# Flight_Controller.net
KiCad netlist of a schematic drawn in EAGLE
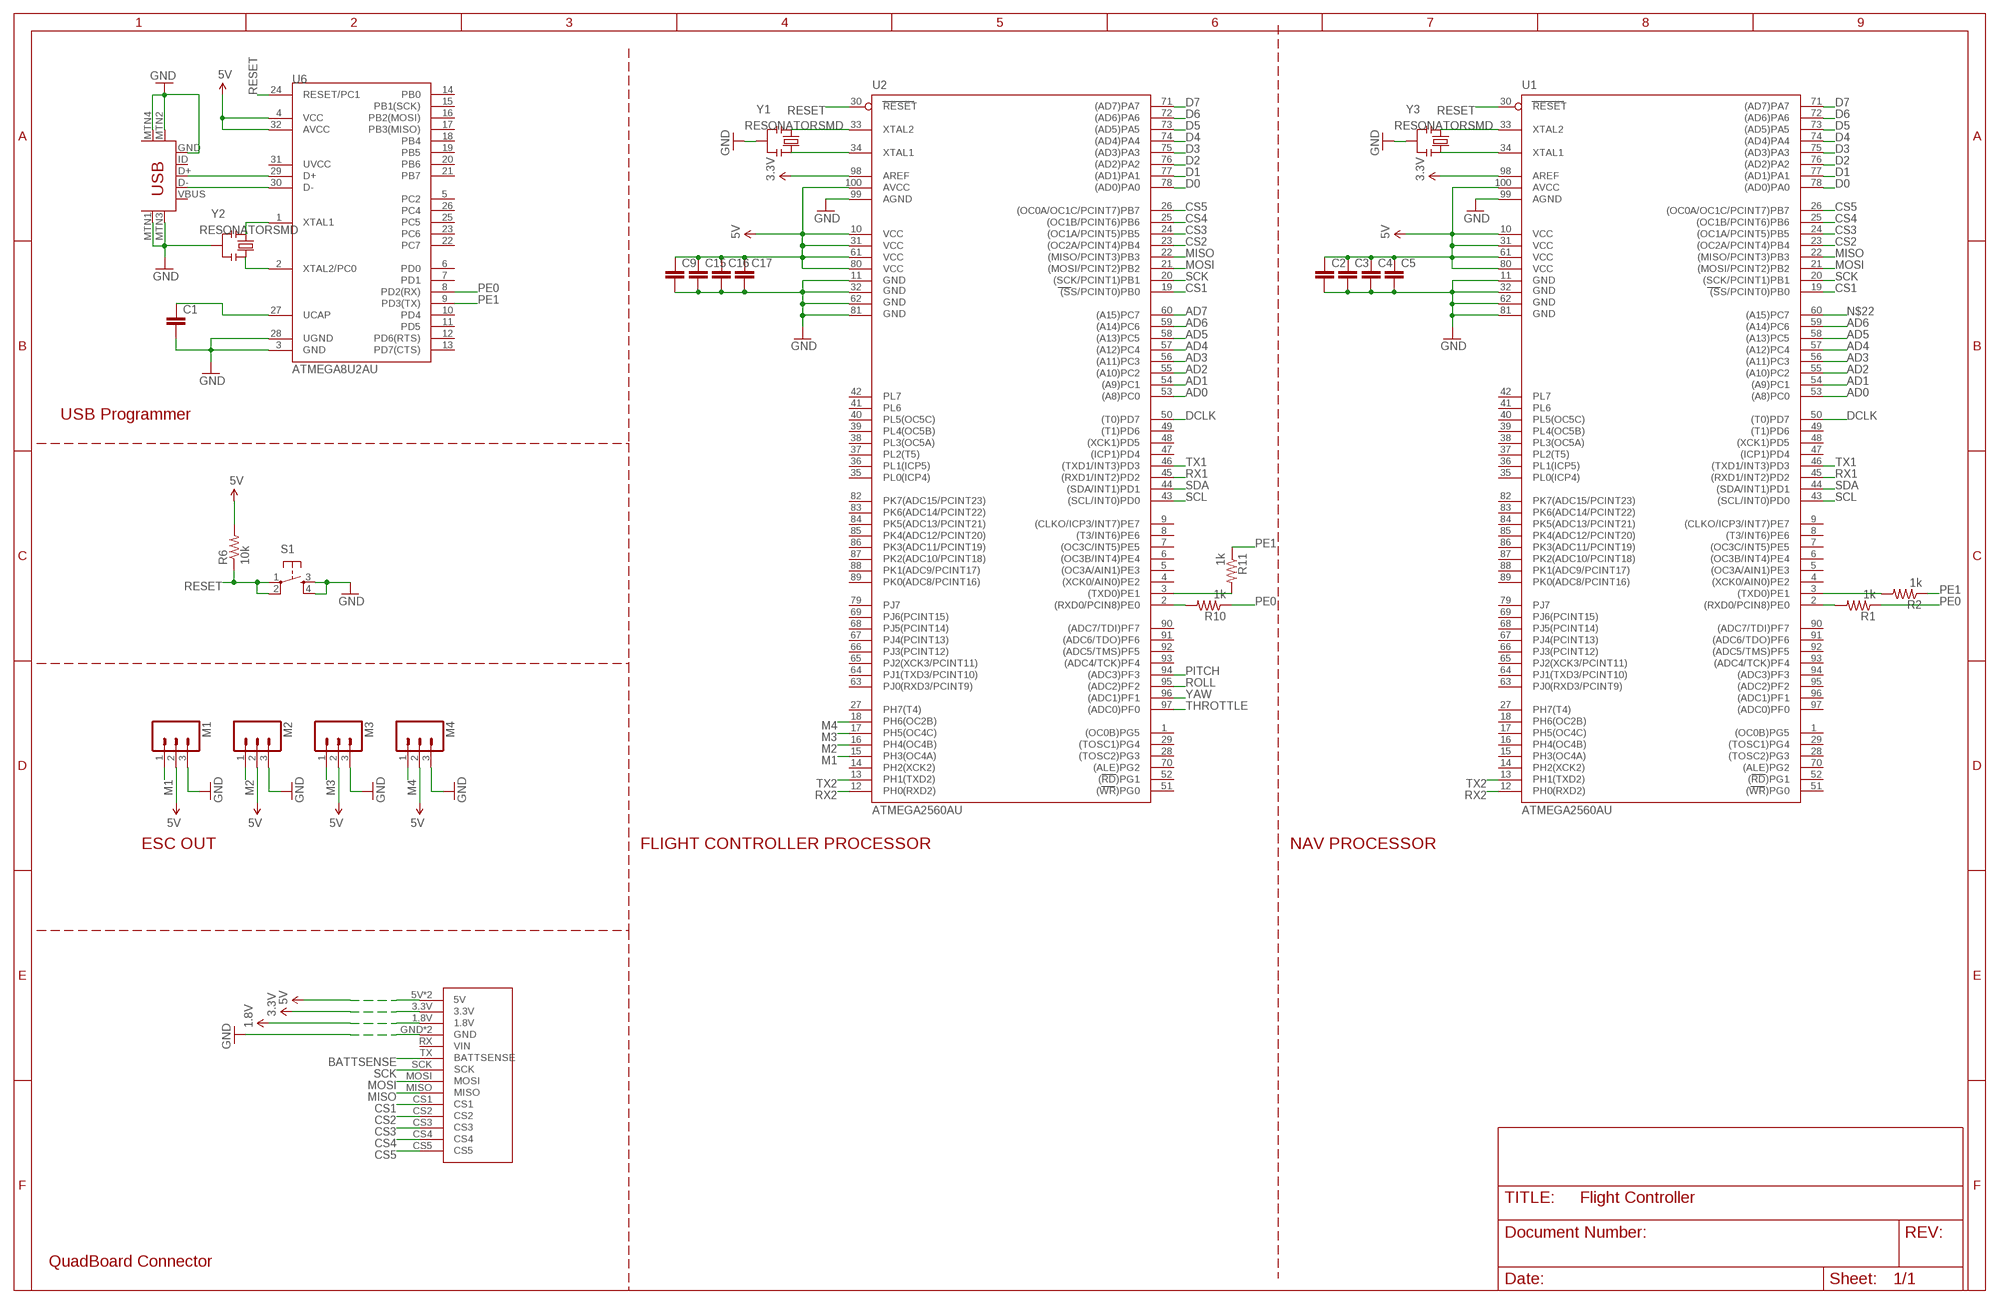
[diagram p0: schematic, sheet 1]

(export (version "E")
  (design (tool "Eeschema 10.0.6"))
  (components
    (comp (ref "C1")
      (value "CAP0805")
      (footprint "eagle-import:0805")
      (libsource (lib "eagle-import") (part "CAP0805"))
    )
    (comp (ref "C2")
      (value "CAP0805")
      (footprint "eagle-import:0805")
      (libsource (lib "eagle-import") (part "CAP0805"))
    )
    (comp (ref "C3")
      (value "CAP0805")
      (footprint "eagle-import:0805")
      (libsource (lib "eagle-import") (part "CAP0805"))
    )
    (comp (ref "C4")
      (value "CAP0805")
      (footprint "eagle-import:0805")
      (libsource (lib "eagle-import") (part "CAP0805"))
    )
    (comp (ref "C5")
      (value "CAP0805")
      (footprint "eagle-import:0805")
      (libsource (lib "eagle-import") (part "CAP0805"))
    )
    (comp (ref "C9")
      (value "CAP0805")
      (footprint "eagle-import:0805")
      (libsource (lib "eagle-import") (part "CAP0805"))
    )
    (comp (ref "C15")
      (value "CAP0805")
      (footprint "eagle-import:0805")
      (libsource (lib "eagle-import") (part "CAP0805"))
    )
    (comp (ref "C16")
      (value "CAP0805")
      (footprint "eagle-import:0805")
      (libsource (lib "eagle-import") (part "CAP0805"))
    )
    (comp (ref "C17")
      (value "CAP0805")
      (footprint "eagle-import:0805")
      (libsource (lib "eagle-import") (part "CAP0805"))
    )
    (comp (ref "M1")
      (value "M03PTH")
      (footprint "eagle-import:1X03")
      (libsource (lib "eagle-import") (part "M03PTH"))
    )
    (comp (ref "M2")
      (value "M03PTH")
      (footprint "eagle-import:1X03")
      (libsource (lib "eagle-import") (part "M03PTH"))
    )
    (comp (ref "M3")
      (value "M03PTH")
      (footprint "eagle-import:1X03")
      (libsource (lib "eagle-import") (part "M03PTH"))
    )
    (comp (ref "M4")
      (value "M03PTH")
      (footprint "eagle-import:1X03")
      (libsource (lib "eagle-import") (part "M03PTH"))
    )
    (comp (ref "R1")
      (value "1k")
      (footprint "eagle-import:0805")
      (libsource (lib "eagle-import") (part "RESISTOR0805-RES"))
    )
    (comp (ref "R2")
      (value "1k")
      (footprint "eagle-import:0805")
      (libsource (lib "eagle-import") (part "RESISTOR0805-RES"))
    )
    (comp (ref "R6")
      (value "10k")
      (footprint "eagle-import:0805")
      (libsource (lib "eagle-import") (part "RESISTOR0805-RES"))
    )
    (comp (ref "R10")
      (value "1k")
      (footprint "eagle-import:0805")
      (libsource (lib "eagle-import") (part "RESISTOR0805-RES"))
    )
    (comp (ref "R11")
      (value "1k")
      (footprint "eagle-import:0805")
      (libsource (lib "eagle-import") (part "RESISTOR0805-RES"))
    )
    (comp (ref "S1")
      (value "TAC_SWITCHSMD")
      (footprint "eagle-import:TACTILE_SWITCH_SMD")
      (libsource (lib "eagle-import") (part "TAC_SWITCHSMD"))
    )
    (comp (ref "U$1")
      (value "QUADBOARDEXT")
      (footprint "eagle-import:QUADBOARDEXT")
      (libsource (lib "eagle-import") (part "QUADBOARDEXT"))
    )
    (comp (ref "U$2")
      (value "USB-MINIB-5PIN")
      (footprint "eagle-import:USB-MINIB")
      (libsource (lib "eagle-import") (part "USB-MINIB-5PIN"))
    )
    (comp (ref "U1")
      (value "ATMEGA2560AU")
      (footprint "eagle-import:TQFP100")
      (libsource (lib "eagle-import") (part "ATMEGA2560AU"))
    )
    (comp (ref "U2")
      (value "ATMEGA2560AU")
      (footprint "eagle-import:TQFP100")
      (libsource (lib "eagle-import") (part "ATMEGA2560AU"))
    )
    (comp (ref "U6")
      (value "ATMEGA8U2AU")
      (footprint "eagle-import:TQFP32-08")
      (libsource (lib "eagle-import") (part "ATMEGA8U2AU"))
    )
    (comp (ref "Y1")
      (value "RESONATORSMD")
      (footprint "eagle-import:RESONATOR-SMD")
      (libsource (lib "eagle-import") (part "RESONATORSMD"))
    )
    (comp (ref "Y2")
      (value "RESONATORSMD")
      (footprint "eagle-import:RESONATOR-SMD")
      (libsource (lib "eagle-import") (part "RESONATORSMD"))
    )
    (comp (ref "Y3")
      (value "RESONATORSMD")
      (footprint "eagle-import:RESONATOR-SMD")
      (libsource (lib "eagle-import") (part "RESONATORSMD"))
    )
  )
  (nets
    (net (code "1") (name "/AD0") (class "Default")
      (node (ref "U1") (pin "53") (pinfunction "(A8)PC0_53") (pintype "bidirectional"))
      (node (ref "U2") (pin "53") (pinfunction "(A8)PC0_53") (pintype "bidirectional"))
    )
    (net (code "2") (name "/AD1") (class "Default")
      (node (ref "U1") (pin "54") (pinfunction "(A9)PC1_54") (pintype "bidirectional"))
      (node (ref "U2") (pin "54") (pinfunction "(A9)PC1_54") (pintype "bidirectional"))
    )
    (net (code "3") (name "/AD2") (class "Default")
      (node (ref "U1") (pin "55") (pinfunction "(A10)PC2_55") (pintype "bidirectional"))
      (node (ref "U2") (pin "55") (pinfunction "(A10)PC2_55") (pintype "bidirectional"))
    )
    (net (code "4") (name "/AD3") (class "Default")
      (node (ref "U1") (pin "56") (pinfunction "(A11)PC3_56") (pintype "bidirectional"))
      (node (ref "U2") (pin "56") (pinfunction "(A11)PC3_56") (pintype "bidirectional"))
    )
    (net (code "5") (name "/AD4") (class "Default")
      (node (ref "U1") (pin "57") (pinfunction "(A12)PC4_57") (pintype "bidirectional"))
      (node (ref "U2") (pin "57") (pinfunction "(A12)PC4_57") (pintype "bidirectional"))
    )
    (net (code "6") (name "/AD5") (class "Default")
      (node (ref "U1") (pin "58") (pinfunction "(A13)PC5_58") (pintype "bidirectional"))
      (node (ref "U2") (pin "58") (pinfunction "(A13)PC5_58") (pintype "bidirectional"))
    )
    (net (code "7") (name "/AD6") (class "Default")
      (node (ref "U1") (pin "59") (pinfunction "(A14)PC6_59") (pintype "bidirectional"))
      (node (ref "U2") (pin "59") (pinfunction "(A14)PC6_59") (pintype "bidirectional"))
    )
    (net (code "8") (name "/AD7") (class "Default")
      (node (ref "U2") (pin "60") (pinfunction "(A15)PC7_60") (pintype "bidirectional"))
    )
    (net (code "9") (name "/BATTSENSE") (class "Default")
      (node (ref "U$1") (pin "TX") (pinfunction "BATTSENSE_TX") (pintype "bidirectional"))
    )
    (net (code "10") (name "/CS1") (class "Default")
      (node (ref "U$1") (pin "CS1") (pinfunction "CS1_CS1") (pintype "bidirectional"))
      (node (ref "U1") (pin "19") (pinfunction "(SS/PCINT0)PB0_19") (pintype "bidirectional"))
      (node (ref "U2") (pin "19") (pinfunction "(SS/PCINT0)PB0_19") (pintype "bidirectional"))
    )
    (net (code "11") (name "/CS2") (class "Default")
      (node (ref "U$1") (pin "CS2") (pinfunction "CS2_CS2") (pintype "bidirectional"))
      (node (ref "U1") (pin "23") (pinfunction "(OC2A/PCINT4)PB4_23") (pintype "bidirectional"))
      (node (ref "U2") (pin "23") (pinfunction "(OC2A/PCINT4)PB4_23") (pintype "bidirectional"))
    )
    (net (code "12") (name "/CS3") (class "Default")
      (node (ref "U$1") (pin "CS3") (pinfunction "CS3_CS3") (pintype "bidirectional"))
      (node (ref "U1") (pin "24") (pinfunction "(OC1A/PCINT5)PB5_24") (pintype "bidirectional"))
      (node (ref "U2") (pin "24") (pinfunction "(OC1A/PCINT5)PB5_24") (pintype "bidirectional"))
    )
    (net (code "13") (name "/CS4") (class "Default")
      (node (ref "U$1") (pin "CS4") (pinfunction "CS4_CS4") (pintype "bidirectional"))
      (node (ref "U1") (pin "25") (pinfunction "(OC1B/PCINT6)PB6_25") (pintype "bidirectional"))
      (node (ref "U2") (pin "25") (pinfunction "(OC1B/PCINT6)PB6_25") (pintype "bidirectional"))
    )
    (net (code "14") (name "/CS5") (class "Default")
      (node (ref "U$1") (pin "CS5") (pinfunction "CS5_CS5") (pintype "bidirectional"))
      (node (ref "U1") (pin "26") (pinfunction "(OC0A/OC1C/PCINT7)PB7_26") (pintype "bidirectional"))
      (node (ref "U2") (pin "26") (pinfunction "(OC0A/OC1C/PCINT7)PB7_26") (pintype "bidirectional"))
    )
    (net (code "15") (name "/D0") (class "Default")
      (node (ref "U1") (pin "78") (pinfunction "(AD0)PA0_78") (pintype "bidirectional"))
      (node (ref "U2") (pin "78") (pinfunction "(AD0)PA0_78") (pintype "bidirectional"))
    )
    (net (code "16") (name "/D1") (class "Default")
      (node (ref "U1") (pin "77") (pinfunction "(AD1)PA1_77") (pintype "bidirectional"))
      (node (ref "U2") (pin "77") (pinfunction "(AD1)PA1_77") (pintype "bidirectional"))
    )
    (net (code "17") (name "/D2") (class "Default")
      (node (ref "U1") (pin "76") (pinfunction "(AD2)PA2_76") (pintype "bidirectional"))
      (node (ref "U2") (pin "76") (pinfunction "(AD2)PA2_76") (pintype "bidirectional"))
    )
    (net (code "18") (name "/D3") (class "Default")
      (node (ref "U1") (pin "75") (pinfunction "(AD3)PA3_75") (pintype "bidirectional"))
      (node (ref "U2") (pin "75") (pinfunction "(AD3)PA3_75") (pintype "bidirectional"))
    )
    (net (code "19") (name "/D4") (class "Default")
      (node (ref "U1") (pin "74") (pinfunction "(AD4)PA4_74") (pintype "bidirectional"))
      (node (ref "U2") (pin "74") (pinfunction "(AD4)PA4_74") (pintype "bidirectional"))
    )
    (net (code "20") (name "/D5") (class "Default")
      (node (ref "U1") (pin "73") (pinfunction "(AD5)PA5_73") (pintype "bidirectional"))
      (node (ref "U2") (pin "73") (pinfunction "(AD5)PA5_73") (pintype "bidirectional"))
    )
    (net (code "21") (name "/D6") (class "Default")
      (node (ref "U1") (pin "72") (pinfunction "(AD6)PA6_72") (pintype "bidirectional"))
      (node (ref "U2") (pin "72") (pinfunction "(AD6)PA6_72") (pintype "bidirectional"))
    )
    (net (code "22") (name "/D7") (class "Default")
      (node (ref "U1") (pin "71") (pinfunction "(AD7)PA7_71") (pintype "bidirectional"))
      (node (ref "U2") (pin "71") (pinfunction "(AD7)PA7_71") (pintype "bidirectional"))
    )
    (net (code "23") (name "/DCLK") (class "Default")
      (node (ref "U1") (pin "50") (pinfunction "(T0)PD7_50") (pintype "bidirectional"))
      (node (ref "U2") (pin "50") (pinfunction "(T0)PD7_50") (pintype "bidirectional"))
    )
    (net (code "24") (name "/M1") (class "Default")
      (node (ref "M1") (pin "1") (pinfunction "1_1") (pintype "passive"))
      (node (ref "U2") (pin "15") (pinfunction "PH3(OC4A)_15") (pintype "bidirectional"))
    )
    (net (code "25") (name "/M2") (class "Default")
      (node (ref "M2") (pin "1") (pinfunction "1_1") (pintype "passive"))
      (node (ref "U2") (pin "16") (pinfunction "PH4(OC4B)_16") (pintype "bidirectional"))
    )
    (net (code "26") (name "/M3") (class "Default")
      (node (ref "M3") (pin "1") (pinfunction "1_1") (pintype "passive"))
      (node (ref "U2") (pin "17") (pinfunction "PH5(OC4C)_17") (pintype "bidirectional"))
    )
    (net (code "27") (name "/M4") (class "Default")
      (node (ref "M4") (pin "1") (pinfunction "1_1") (pintype "passive"))
      (node (ref "U2") (pin "18") (pinfunction "PH6(OC2B)_18") (pintype "bidirectional"))
    )
    (net (code "28") (name "/MISO") (class "Default")
      (node (ref "U$1") (pin "MISO") (pinfunction "MISO_MISO") (pintype "bidirectional"))
      (node (ref "U1") (pin "22") (pinfunction "(MISO/PCINT3)PB3_22") (pintype "bidirectional"))
      (node (ref "U2") (pin "22") (pinfunction "(MISO/PCINT3)PB3_22") (pintype "bidirectional"))
    )
    (net (code "29") (name "/MOSI") (class "Default")
      (node (ref "U$1") (pin "MOSI") (pinfunction "MOSI_MOSI") (pintype "bidirectional"))
      (node (ref "U1") (pin "21") (pinfunction "(MOSI/PCINT2)PB2_21") (pintype "bidirectional"))
      (node (ref "U2") (pin "21") (pinfunction "(MOSI/PCINT2)PB2_21") (pintype "bidirectional"))
    )
    (net (code "30") (name "/N$22") (class "Default")
      (node (ref "U1") (pin "60") (pinfunction "(A15)PC7_60") (pintype "bidirectional"))
    )
    (net (code "31") (name "/PE0") (class "Default")
      (node (ref "R1") (pin "1") (pinfunction "1_1") (pintype "passive"))
      (node (ref "R10") (pin "1") (pinfunction "1_1") (pintype "passive"))
      (node (ref "U6") (pin "8") (pinfunction "PD2(RX)_8") (pintype "bidirectional"))
    )
    (net (code "32") (name "/PE1") (class "Default")
      (node (ref "R11") (pin "1") (pinfunction "1_1") (pintype "passive"))
      (node (ref "R2") (pin "1") (pinfunction "1_1") (pintype "passive"))
      (node (ref "U6") (pin "9") (pinfunction "PD3(TX)_9") (pintype "bidirectional"))
    )
    (net (code "33") (name "/PITCH") (class "Default")
      (node (ref "U2") (pin "94") (pinfunction "(ADC3)PF3_94") (pintype "bidirectional"))
    )
    (net (code "34") (name "/RESET") (class "Default")
      (node (ref "R6") (pin "1") (pinfunction "1_1") (pintype "passive"))
      (node (ref "S1") (pin "1") (pinfunction "1_1") (pintype "passive"))
      (node (ref "S1") (pin "2") (pinfunction "2_2") (pintype "passive"))
      (node (ref "U1") (pin "30") (pinfunction "RESET_30") (pintype "input"))
      (node (ref "U2") (pin "30") (pinfunction "RESET_30") (pintype "input"))
      (node (ref "U6") (pin "24") (pinfunction "RESET/PC1_24") (pintype "bidirectional"))
    )
    (net (code "35") (name "/ROLL") (class "Default")
      (node (ref "U2") (pin "95") (pinfunction "(ADC2)PF2_95") (pintype "bidirectional"))
    )
    (net (code "36") (name "/RX1") (class "Default")
      (node (ref "U1") (pin "45") (pinfunction "(RXD1/INT2)PD2_45") (pintype "bidirectional"))
      (node (ref "U2") (pin "45") (pinfunction "(RXD1/INT2)PD2_45") (pintype "bidirectional"))
    )
    (net (code "37") (name "/RX2") (class "Default")
      (node (ref "U1") (pin "12") (pinfunction "PH0(RXD2)_12") (pintype "bidirectional"))
      (node (ref "U2") (pin "12") (pinfunction "PH0(RXD2)_12") (pintype "bidirectional"))
    )
    (net (code "38") (name "/SCK") (class "Default")
      (node (ref "U$1") (pin "SCK") (pinfunction "SCK_SCK") (pintype "bidirectional"))
      (node (ref "U1") (pin "20") (pinfunction "(SCK/PCINT1)PB1_20") (pintype "bidirectional"))
      (node (ref "U2") (pin "20") (pinfunction "(SCK/PCINT1)PB1_20") (pintype "bidirectional"))
    )
    (net (code "39") (name "/SCL") (class "Default")
      (node (ref "U1") (pin "43") (pinfunction "(SCL/INT0)PD0_43") (pintype "bidirectional"))
      (node (ref "U2") (pin "43") (pinfunction "(SCL/INT0)PD0_43") (pintype "bidirectional"))
    )
    (net (code "40") (name "/SDA") (class "Default")
      (node (ref "U1") (pin "44") (pinfunction "(SDA/INT1)PD1_44") (pintype "bidirectional"))
      (node (ref "U2") (pin "44") (pinfunction "(SDA/INT1)PD1_44") (pintype "bidirectional"))
    )
    (net (code "41") (name "/THROTTLE") (class "Default")
      (node (ref "U2") (pin "97") (pinfunction "(ADC0)PF0_97") (pintype "bidirectional"))
    )
    (net (code "42") (name "/TX1") (class "Default")
      (node (ref "U1") (pin "46") (pinfunction "(TXD1/INT3)PD3_46") (pintype "bidirectional"))
      (node (ref "U2") (pin "46") (pinfunction "(TXD1/INT3)PD3_46") (pintype "bidirectional"))
    )
    (net (code "43") (name "/TX2") (class "Default")
      (node (ref "U1") (pin "13") (pinfunction "PH1(TXD2)_13") (pintype "bidirectional"))
      (node (ref "U2") (pin "13") (pinfunction "PH1(TXD2)_13") (pintype "bidirectional"))
    )
    (net (code "44") (name "/YAW") (class "Default")
      (node (ref "U2") (pin "96") (pinfunction "(ADC1)PF1_96") (pintype "bidirectional"))
    )
    (net (code "45") (name "1.8V") (class "Default")
      (node (ref "U$1") (pin "1.8V") (pinfunction "1.8V_1.8V") (pintype "bidirectional"))
    )
    (net (code "46") (name "3.3V") (class "Default")
      (node (ref "U$1") (pin "3.3V") (pinfunction "3.3V_3.3V") (pintype "bidirectional"))
      (node (ref "U1") (pin "98") (pinfunction "AREF_98") (pintype "bidirectional"))
      (node (ref "U2") (pin "98") (pinfunction "AREF_98") (pintype "bidirectional"))
    )
    (net (code "47") (name "5V") (class "Default")
      (node (ref "C15") (pin "1") (pinfunction "1_1") (pintype "passive"))
      (node (ref "C16") (pin "1") (pinfunction "1_1") (pintype "passive"))
      (node (ref "C17") (pin "1") (pinfunction "1_1") (pintype "passive"))
      (node (ref "C2") (pin "1") (pinfunction "1_1") (pintype "passive"))
      (node (ref "C3") (pin "1") (pinfunction "1_1") (pintype "passive"))
      (node (ref "C4") (pin "1") (pinfunction "1_1") (pintype "passive"))
      (node (ref "C5") (pin "1") (pinfunction "1_1") (pintype "passive"))
      (node (ref "C9") (pin "1") (pinfunction "1_1") (pintype "passive"))
      (node (ref "M1") (pin "2") (pinfunction "2_2") (pintype "passive"))
      (node (ref "M2") (pin "2") (pinfunction "2_2") (pintype "passive"))
      (node (ref "M3") (pin "2") (pinfunction "2_2") (pintype "passive"))
      (node (ref "M4") (pin "2") (pinfunction "2_2") (pintype "passive"))
      (node (ref "R6") (pin "2") (pinfunction "2_2") (pintype "passive"))
      (node (ref "U$1") (pin "5V") (pinfunction "5V_5V") (pintype "bidirectional"))
      (node (ref "U$1") (pin "5V1") (pinfunction "5V_5V1") (pintype "bidirectional"))
      (node (ref "U1") (pin "10") (pinfunction "VCC_10") (pintype "power_in"))
      (node (ref "U1") (pin "100") (pinfunction "AVCC_100") (pintype "power_in"))
      (node (ref "U1") (pin "31") (pinfunction "VCC1_31") (pintype "power_in"))
      (node (ref "U1") (pin "61") (pinfunction "VCC2_61") (pintype "power_in"))
      (node (ref "U1") (pin "80") (pinfunction "VCC3_80") (pintype "power_in"))
      (node (ref "U2") (pin "10") (pinfunction "VCC_10") (pintype "power_in"))
      (node (ref "U2") (pin "100") (pinfunction "AVCC_100") (pintype "power_in"))
      (node (ref "U2") (pin "31") (pinfunction "VCC1_31") (pintype "power_in"))
      (node (ref "U2") (pin "61") (pinfunction "VCC2_61") (pintype "power_in"))
      (node (ref "U2") (pin "80") (pinfunction "VCC3_80") (pintype "power_in"))
      (node (ref "U6") (pin "32") (pinfunction "AVCC_32") (pintype "bidirectional"))
      (node (ref "U6") (pin "4") (pinfunction "VCC_4") (pintype "bidirectional"))
    )
    (net (code "48") (name "GND") (class "Default")
      (node (ref "C1") (pin "2") (pinfunction "2_2") (pintype "passive"))
      (node (ref "C15") (pin "2") (pinfunction "2_2") (pintype "passive"))
      (node (ref "C16") (pin "2") (pinfunction "2_2") (pintype "passive"))
      (node (ref "C17") (pin "2") (pinfunction "2_2") (pintype "passive"))
      (node (ref "C2") (pin "2") (pinfunction "2_2") (pintype "passive"))
      (node (ref "C3") (pin "2") (pinfunction "2_2") (pintype "passive"))
      (node (ref "C4") (pin "2") (pinfunction "2_2") (pintype "passive"))
      (node (ref "C5") (pin "2") (pinfunction "2_2") (pintype "passive"))
      (node (ref "C9") (pin "2") (pinfunction "2_2") (pintype "passive"))
      (node (ref "M1") (pin "3") (pinfunction "3_3") (pintype "passive"))
      (node (ref "M2") (pin "3") (pinfunction "3_3") (pintype "passive"))
      (node (ref "M3") (pin "3") (pinfunction "3_3") (pintype "passive"))
      (node (ref "M4") (pin "3") (pinfunction "3_3") (pintype "passive"))
      (node (ref "S1") (pin "3") (pinfunction "3_3") (pintype "passive"))
      (node (ref "S1") (pin "4") (pinfunction "4_4") (pintype "passive"))
      (node (ref "U$1") (pin "GND") (pinfunction "GND_GND") (pintype "bidirectional"))
      (node (ref "U$1") (pin "GND1") (pinfunction "GND_GND1") (pintype "bidirectional"))
      (node (ref "U$2") (pin "GND") (pinfunction "GND_GND") (pintype "bidirectional"))
      (node (ref "U$2") (pin "MTN1") (pinfunction "MTN2_MTN1") (pintype "bidirectional"))
      (node (ref "U$2") (pin "MTN2") (pinfunction "MTN3_MTN2") (pintype "bidirectional"))
      (node (ref "U$2") (pin "MTN3") (pinfunction "MTN1_MTN3") (pintype "bidirectional"))
      (node (ref "U$2") (pin "MTN4") (pinfunction "MTN4_MTN4") (pintype "bidirectional"))
      (node (ref "U1") (pin "11") (pinfunction "GND_11") (pintype "power_in"))
      (node (ref "U1") (pin "32") (pinfunction "GND1_32") (pintype "power_in"))
      (node (ref "U1") (pin "62") (pinfunction "GND2_62") (pintype "power_in"))
      (node (ref "U1") (pin "81") (pinfunction "GND3_81") (pintype "power_in"))
      (node (ref "U1") (pin "99") (pinfunction "AGND_99") (pintype "power_in"))
      (node (ref "U2") (pin "11") (pinfunction "GND_11") (pintype "power_in"))
      (node (ref "U2") (pin "32") (pinfunction "GND1_32") (pintype "power_in"))
      (node (ref "U2") (pin "62") (pinfunction "GND2_62") (pintype "power_in"))
      (node (ref "U2") (pin "81") (pinfunction "GND3_81") (pintype "power_in"))
      (node (ref "U2") (pin "99") (pinfunction "AGND_99") (pintype "power_in"))
      (node (ref "U6") (pin "28") (pinfunction "UGND_28") (pintype "bidirectional"))
      (node (ref "U6") (pin "3") (pinfunction "GND_3") (pintype "bidirectional"))
      (node (ref "Y1") (pin "2") (pinfunction "2_2") (pintype "passive"))
      (node (ref "Y2") (pin "2") (pinfunction "2_2") (pintype "passive"))
      (node (ref "Y3") (pin "2") (pinfunction "2_2") (pintype "passive"))
    )
    (net (code "49") (name "Net-(U1-(RXD0{slash}PCIN8)PE0)") (class "Default")
      (node (ref "R1") (pin "2") (pinfunction "2_2") (pintype "passive"))
      (node (ref "U1") (pin "2") (pinfunction "(RXD0/PCIN8)PE0_2") (pintype "bidirectional"))
    )
    (net (code "50") (name "Net-(U1-(TXD0)PE1)") (class "Default")
      (node (ref "R2") (pin "2") (pinfunction "2_2") (pintype "passive"))
      (node (ref "U1") (pin "3") (pinfunction "(TXD0)PE1_3") (pintype "bidirectional"))
    )
    (net (code "51") (name "Net-(U1-XTAL1)") (class "Default")
      (node (ref "U1") (pin "34") (pinfunction "XTAL1_34") (pintype "input"))
      (node (ref "Y3") (pin "3") (pinfunction "3_3") (pintype "passive"))
    )
    (net (code "52") (name "Net-(U1-XTAL2)") (class "Default")
      (node (ref "U1") (pin "33") (pinfunction "XTAL2_33") (pintype "output"))
      (node (ref "Y3") (pin "1") (pinfunction "1_1") (pintype "passive"))
    )
    (net (code "53") (name "Net-(U2-(RXD0{slash}PCIN8)PE0)") (class "Default")
      (node (ref "R10") (pin "2") (pinfunction "2_2") (pintype "passive"))
      (node (ref "U2") (pin "2") (pinfunction "(RXD0/PCIN8)PE0_2") (pintype "bidirectional"))
    )
    (net (code "54") (name "Net-(U2-(TXD0)PE1)") (class "Default")
      (node (ref "R11") (pin "2") (pinfunction "2_2") (pintype "passive"))
      (node (ref "U2") (pin "3") (pinfunction "(TXD0)PE1_3") (pintype "bidirectional"))
    )
    (net (code "55") (name "Net-(U2-XTAL1)") (class "Default")
      (node (ref "U2") (pin "34") (pinfunction "XTAL1_34") (pintype "input"))
      (node (ref "Y1") (pin "3") (pinfunction "3_3") (pintype "passive"))
    )
    (net (code "56") (name "Net-(U2-XTAL2)") (class "Default")
      (node (ref "U2") (pin "33") (pinfunction "XTAL2_33") (pintype "output"))
      (node (ref "Y1") (pin "1") (pinfunction "1_1") (pintype "passive"))
    )
    (net (code "57") (name "Net-(U6-D+)") (class "Default")
      (node (ref "U$2") (pin "D+") (pinfunction "D+_D+") (pintype "bidirectional"))
      (node (ref "U6") (pin "29") (pinfunction "D+_29") (pintype "bidirectional"))
    )
    (net (code "58") (name "Net-(U6-D-)") (class "Default")
      (node (ref "U$2") (pin "D-") (pinfunction "D-_D-") (pintype "bidirectional"))
      (node (ref "U6") (pin "30") (pinfunction "D-_30") (pintype "bidirectional"))
    )
    (net (code "59") (name "Net-(U6-UCAP)") (class "Default")
      (node (ref "C1") (pin "1") (pinfunction "1_1") (pintype "passive"))
      (node (ref "U6") (pin "27") (pinfunction "UCAP_27") (pintype "bidirectional"))
    )
    (net (code "60") (name "Net-(U6-XTAL1)") (class "Default")
      (node (ref "U6") (pin "1") (pinfunction "XTAL1_1") (pintype "bidirectional"))
      (node (ref "Y2") (pin "1") (pinfunction "1_1") (pintype "passive"))
    )
    (net (code "61") (name "Net-(U6-XTAL2{slash}PC0)") (class "Default")
      (node (ref "U6") (pin "2") (pinfunction "XTAL2/PC0_2") (pintype "bidirectional"))
      (node (ref "Y2") (pin "3") (pinfunction "3_3") (pintype "passive"))
    )
    (net (code "62") (name "unconnected-(U$1-VIN-PadRX)") (class "Default")
      (node (ref "U$1") (pin "RX") (pinfunction "VIN_RX") (pintype "bidirectional"))
    )
    (net (code "63") (name "unconnected-(U$2-PadID)") (class "Default")
      (node (ref "U$2") (pin "ID") (pinfunction "ID_ID") (pintype "bidirectional"))
    )
    (net (code "64") (name "unconnected-(U$2-PadVBUS)") (class "Default")
      (node (ref "U$2") (pin "VBUS") (pinfunction "VBUS_VBUS") (pintype "bidirectional"))
    )
    (net (code "65") (name "unconnected-(U1-(ADC0)PF0-Pad97)") (class "Default")
      (node (ref "U1") (pin "97") (pinfunction "(ADC0)PF0_97") (pintype "bidirectional"))
    )
    (net (code "66") (name "unconnected-(U1-(ADC1)PF1-Pad96)") (class "Default")
      (node (ref "U1") (pin "96") (pinfunction "(ADC1)PF1_96") (pintype "bidirectional"))
    )
    (net (code "67") (name "unconnected-(U1-(ADC2)PF2-Pad95)") (class "Default")
      (node (ref "U1") (pin "95") (pinfunction "(ADC2)PF2_95") (pintype "bidirectional"))
    )
    (net (code "68") (name "unconnected-(U1-(ADC3)PF3-Pad94)") (class "Default")
      (node (ref "U1") (pin "94") (pinfunction "(ADC3)PF3_94") (pintype "bidirectional"))
    )
    (net (code "69") (name "unconnected-(U1-(ADC4{slash}TCK)PF4-Pad93)") (class "Default")
      (node (ref "U1") (pin "93") (pinfunction "(ADC4/TCK)PF4_93") (pintype "bidirectional"))
    )
    (net (code "70") (name "unconnected-(U1-(ADC5{slash}TMS)PF5-Pad92)") (class "Default")
      (node (ref "U1") (pin "92") (pinfunction "(ADC5/TMS)PF5_92") (pintype "bidirectional"))
    )
    (net (code "71") (name "unconnected-(U1-(ADC6{slash}TDO)PF6-Pad91)") (class "Default")
      (node (ref "U1") (pin "91") (pinfunction "(ADC6/TDO)PF6_91") (pintype "bidirectional"))
    )
    (net (code "72") (name "unconnected-(U1-(ADC7{slash}TDI)PF7-Pad90)") (class "Default")
      (node (ref "U1") (pin "90") (pinfunction "(ADC7/TDI)PF7_90") (pintype "bidirectional"))
    )
    (net (code "73") (name "unconnected-(U1-(ALE)PG2-Pad70)") (class "Default")
      (node (ref "U1") (pin "70") (pinfunction "(ALE)PG2_70") (pintype "bidirectional"))
    )
    (net (code "74") (name "unconnected-(U1-(CLKO{slash}ICP3{slash}INT7)PE7-Pad9)") (class "Default")
      (node (ref "U1") (pin "9") (pinfunction "(CLKO/ICP3/INT7)PE7_9") (pintype "bidirectional"))
    )
    (net (code "75") (name "unconnected-(U1-(ICP1)PD4-Pad47)") (class "Default")
      (node (ref "U1") (pin "47") (pinfunction "(ICP1)PD4_47") (pintype "bidirectional"))
    )
    (net (code "76") (name "unconnected-(U1-(OC0B)PG5-Pad1)") (class "Default")
      (node (ref "U1") (pin "1") (pinfunction "(OC0B)PG5_1") (pintype "bidirectional"))
    )
    (net (code "77") (name "unconnected-(U1-(OC3A{slash}AIN1)PE3-Pad5)") (class "Default")
      (node (ref "U1") (pin "5") (pinfunction "(OC3A/AIN1)PE3_5") (pintype "bidirectional"))
    )
    (net (code "78") (name "unconnected-(U1-(OC3B{slash}INT4)PE4-Pad6)") (class "Default")
      (node (ref "U1") (pin "6") (pinfunction "(OC3B/INT4)PE4_6") (pintype "bidirectional"))
    )
    (net (code "79") (name "unconnected-(U1-(OC3C{slash}INT5)PE5-Pad7)") (class "Default")
      (node (ref "U1") (pin "7") (pinfunction "(OC3C/INT5)PE5_7") (pintype "bidirectional"))
    )
    (net (code "80") (name "unconnected-(U1-(RD)PG1-Pad52)") (class "Default")
      (node (ref "U1") (pin "52") (pinfunction "(RD)PG1_52") (pintype "bidirectional"))
    )
    (net (code "81") (name "unconnected-(U1-(T1)PD6-Pad49)") (class "Default")
      (node (ref "U1") (pin "49") (pinfunction "(T1)PD6_49") (pintype "bidirectional"))
    )
    (net (code "82") (name "unconnected-(U1-(T3{slash}INT6)PE6-Pad8)") (class "Default")
      (node (ref "U1") (pin "8") (pinfunction "(T3/INT6)PE6_8") (pintype "bidirectional"))
    )
    (net (code "83") (name "unconnected-(U1-(TOSC1)PG4-Pad29)") (class "Default")
      (node (ref "U1") (pin "29") (pinfunction "(TOSC1)PG4_29") (pintype "bidirectional"))
    )
    (net (code "84") (name "unconnected-(U1-(TOSC2)PG3-Pad28)") (class "Default")
      (node (ref "U1") (pin "28") (pinfunction "(TOSC2)PG3_28") (pintype "bidirectional"))
    )
    (net (code "85") (name "unconnected-(U1-(WR)PG0-Pad51)") (class "Default")
      (node (ref "U1") (pin "51") (pinfunction "(WR)PG0_51") (pintype "bidirectional"))
    )
    (net (code "86") (name "unconnected-(U1-(XCK0{slash}AIN0)PE2-Pad4)") (class "Default")
      (node (ref "U1") (pin "4") (pinfunction "(XCK0/AIN0)PE2_4") (pintype "bidirectional"))
    )
    (net (code "87") (name "unconnected-(U1-(XCK1)PD5-Pad48)") (class "Default")
      (node (ref "U1") (pin "48") (pinfunction "(XCK1)PD5_48") (pintype "bidirectional"))
    )
    (net (code "88") (name "unconnected-(U1-PH2(XCK2)-Pad14)") (class "Default")
      (node (ref "U1") (pin "14") (pinfunction "PH2(XCK2)_14") (pintype "bidirectional"))
    )
    (net (code "89") (name "unconnected-(U1-PH3(OC4A)-Pad15)") (class "Default")
      (node (ref "U1") (pin "15") (pinfunction "PH3(OC4A)_15") (pintype "bidirectional"))
    )
    (net (code "90") (name "unconnected-(U1-PH4(OC4B)-Pad16)") (class "Default")
      (node (ref "U1") (pin "16") (pinfunction "PH4(OC4B)_16") (pintype "bidirectional"))
    )
    (net (code "91") (name "unconnected-(U1-PH5(OC4C)-Pad17)") (class "Default")
      (node (ref "U1") (pin "17") (pinfunction "PH5(OC4C)_17") (pintype "bidirectional"))
    )
    (net (code "92") (name "unconnected-(U1-PH6(OC2B)-Pad18)") (class "Default")
      (node (ref "U1") (pin "18") (pinfunction "PH6(OC2B)_18") (pintype "bidirectional"))
    )
    (net (code "93") (name "unconnected-(U1-PH7(T4)-Pad27)") (class "Default")
      (node (ref "U1") (pin "27") (pinfunction "PH7(T4)_27") (pintype "bidirectional"))
    )
    (net (code "94") (name "unconnected-(U1-PJ0(RXD3{slash}PCINT9)-Pad63)") (class "Default")
      (node (ref "U1") (pin "63") (pinfunction "PJ0(RXD3/PCINT9)_63") (pintype "bidirectional"))
    )
    (net (code "95") (name "unconnected-(U1-PJ1(TXD3{slash}PCINT10)-Pad64)") (class "Default")
      (node (ref "U1") (pin "64") (pinfunction "PJ1(TXD3/PCINT10)_64") (pintype "bidirectional"))
    )
    (net (code "96") (name "unconnected-(U1-PJ2(XCK3{slash}PCINT11)-Pad65)") (class "Default")
      (node (ref "U1") (pin "65") (pinfunction "PJ2(XCK3/PCINT11)_65") (pintype "bidirectional"))
    )
    (net (code "97") (name "unconnected-(U1-PJ3(PCINT12)-Pad66)") (class "Default")
      (node (ref "U1") (pin "66") (pinfunction "PJ3(PCINT12)_66") (pintype "bidirectional"))
    )
    (net (code "98") (name "unconnected-(U1-PJ4(PCINT13)-Pad67)") (class "Default")
      (node (ref "U1") (pin "67") (pinfunction "PJ4(PCINT13)_67") (pintype "bidirectional"))
    )
    (net (code "99") (name "unconnected-(U1-PJ5(PCINT14)-Pad68)") (class "Default")
      (node (ref "U1") (pin "68") (pinfunction "PJ5(PCINT14)_68") (pintype "bidirectional"))
    )
    (net (code "100") (name "unconnected-(U1-PJ6(PCINT15)-Pad69)") (class "Default")
      (node (ref "U1") (pin "69") (pinfunction "PJ6(PCINT15)_69") (pintype "bidirectional"))
    )
    (net (code "101") (name "unconnected-(U1-PJ7-Pad79)") (class "Default")
      (node (ref "U1") (pin "79") (pinfunction "PJ7_79") (pintype "bidirectional"))
    )
    (net (code "102") (name "unconnected-(U1-PK0(ADC8{slash}PCINT16)-Pad89)") (class "Default")
      (node (ref "U1") (pin "89") (pinfunction "PK0(ADC8/PCINT16)_89") (pintype "bidirectional"))
    )
    (net (code "103") (name "unconnected-(U1-PK1(ADC9{slash}PCINT17)-Pad88)") (class "Default")
      (node (ref "U1") (pin "88") (pinfunction "PK1(ADC9/PCINT17)_88") (pintype "bidirectional"))
    )
    (net (code "104") (name "unconnected-(U1-PK2(ADC10{slash}PCINT18)-Pad87)") (class "Default")
      (node (ref "U1") (pin "87") (pinfunction "PK2(ADC10/PCINT18)_87") (pintype "bidirectional"))
    )
    (net (code "105") (name "unconnected-(U1-PK3(ADC11{slash}PCINT19)-Pad86)") (class "Default")
      (node (ref "U1") (pin "86") (pinfunction "PK3(ADC11/PCINT19)_86") (pintype "bidirectional"))
    )
    (net (code "106") (name "unconnected-(U1-PK4(ADC12{slash}PCINT20)-Pad85)") (class "Default")
      (node (ref "U1") (pin "85") (pinfunction "PK4(ADC12/PCINT20)_85") (pintype "bidirectional"))
    )
    (net (code "107") (name "unconnected-(U1-PK5(ADC13{slash}PCINT21)-Pad84)") (class "Default")
      (node (ref "U1") (pin "84") (pinfunction "PK5(ADC13/PCINT21)_84") (pintype "bidirectional"))
    )
    (net (code "108") (name "unconnected-(U1-PK6(ADC14{slash}PCINT22)-Pad83)") (class "Default")
      (node (ref "U1") (pin "83") (pinfunction "PK6(ADC14/PCINT22)_83") (pintype "bidirectional"))
    )
    (net (code "109") (name "unconnected-(U1-PK7(ADC15{slash}PCINT23)-Pad82)") (class "Default")
      (node (ref "U1") (pin "82") (pinfunction "PK7(ADC15/PCINT23)_82") (pintype "bidirectional"))
    )
    (net (code "110") (name "unconnected-(U1-PL0(ICP4)-Pad35)") (class "Default")
      (node (ref "U1") (pin "35") (pinfunction "PL0(ICP4)_35") (pintype "bidirectional"))
    )
    (net (code "111") (name "unconnected-(U1-PL1(ICP5)-Pad36)") (class "Default")
      (node (ref "U1") (pin "36") (pinfunction "PL1(ICP5)_36") (pintype "bidirectional"))
    )
    (net (code "112") (name "unconnected-(U1-PL2(T5)-Pad37)") (class "Default")
      (node (ref "U1") (pin "37") (pinfunction "PL2(T5)_37") (pintype "bidirectional"))
    )
    (net (code "113") (name "unconnected-(U1-PL3(OC5A)-Pad38)") (class "Default")
      (node (ref "U1") (pin "38") (pinfunction "PL3(OC5A)_38") (pintype "bidirectional"))
    )
    (net (code "114") (name "unconnected-(U1-PL4(OC5B)-Pad39)") (class "Default")
      (node (ref "U1") (pin "39") (pinfunction "PL4(OC5B)_39") (pintype "bidirectional"))
    )
    (net (code "115") (name "unconnected-(U1-PL5(OC5C)-Pad40)") (class "Default")
      (node (ref "U1") (pin "40") (pinfunction "PL5(OC5C)_40") (pintype "bidirectional"))
    )
    (net (code "116") (name "unconnected-(U1-PL6-Pad41)") (class "Default")
      (node (ref "U1") (pin "41") (pinfunction "PL6_41") (pintype "bidirectional"))
    )
    (net (code "117") (name "unconnected-(U1-PL7-Pad42)") (class "Default")
      (node (ref "U1") (pin "42") (pinfunction "PL7_42") (pintype "bidirectional"))
    )
    (net (code "118") (name "unconnected-(U2-(ADC4{slash}TCK)PF4-Pad93)") (class "Default")
      (node (ref "U2") (pin "93") (pinfunction "(ADC4/TCK)PF4_93") (pintype "bidirectional"))
    )
    (net (code "119") (name "unconnected-(U2-(ADC5{slash}TMS)PF5-Pad92)") (class "Default")
      (node (ref "U2") (pin "92") (pinfunction "(ADC5/TMS)PF5_92") (pintype "bidirectional"))
    )
    (net (code "120") (name "unconnected-(U2-(ADC6{slash}TDO)PF6-Pad91)") (class "Default")
      (node (ref "U2") (pin "91") (pinfunction "(ADC6/TDO)PF6_91") (pintype "bidirectional"))
    )
    (net (code "121") (name "unconnected-(U2-(ADC7{slash}TDI)PF7-Pad90)") (class "Default")
      (node (ref "U2") (pin "90") (pinfunction "(ADC7/TDI)PF7_90") (pintype "bidirectional"))
    )
    (net (code "122") (name "unconnected-(U2-(ALE)PG2-Pad70)") (class "Default")
      (node (ref "U2") (pin "70") (pinfunction "(ALE)PG2_70") (pintype "bidirectional"))
    )
    (net (code "123") (name "unconnected-(U2-(CLKO{slash}ICP3{slash}INT7)PE7-Pad9)") (class "Default")
      (node (ref "U2") (pin "9") (pinfunction "(CLKO/ICP3/INT7)PE7_9") (pintype "bidirectional"))
    )
    (net (code "124") (name "unconnected-(U2-(ICP1)PD4-Pad47)") (class "Default")
      (node (ref "U2") (pin "47") (pinfunction "(ICP1)PD4_47") (pintype "bidirectional"))
    )
    (net (code "125") (name "unconnected-(U2-(OC0B)PG5-Pad1)") (class "Default")
      (node (ref "U2") (pin "1") (pinfunction "(OC0B)PG5_1") (pintype "bidirectional"))
    )
    (net (code "126") (name "unconnected-(U2-(OC3A{slash}AIN1)PE3-Pad5)") (class "Default")
      (node (ref "U2") (pin "5") (pinfunction "(OC3A/AIN1)PE3_5") (pintype "bidirectional"))
    )
    (net (code "127") (name "unconnected-(U2-(OC3B{slash}INT4)PE4-Pad6)") (class "Default")
      (node (ref "U2") (pin "6") (pinfunction "(OC3B/INT4)PE4_6") (pintype "bidirectional"))
    )
    (net (code "128") (name "unconnected-(U2-(OC3C{slash}INT5)PE5-Pad7)") (class "Default")
      (node (ref "U2") (pin "7") (pinfunction "(OC3C/INT5)PE5_7") (pintype "bidirectional"))
    )
    (net (code "129") (name "unconnected-(U2-(RD)PG1-Pad52)") (class "Default")
      (node (ref "U2") (pin "52") (pinfunction "(RD)PG1_52") (pintype "bidirectional"))
    )
    (net (code "130") (name "unconnected-(U2-(T1)PD6-Pad49)") (class "Default")
      (node (ref "U2") (pin "49") (pinfunction "(T1)PD6_49") (pintype "bidirectional"))
    )
    (net (code "131") (name "unconnected-(U2-(T3{slash}INT6)PE6-Pad8)") (class "Default")
      (node (ref "U2") (pin "8") (pinfunction "(T3/INT6)PE6_8") (pintype "bidirectional"))
    )
    (net (code "132") (name "unconnected-(U2-(TOSC1)PG4-Pad29)") (class "Default")
      (node (ref "U2") (pin "29") (pinfunction "(TOSC1)PG4_29") (pintype "bidirectional"))
    )
    (net (code "133") (name "unconnected-(U2-(TOSC2)PG3-Pad28)") (class "Default")
      (node (ref "U2") (pin "28") (pinfunction "(TOSC2)PG3_28") (pintype "bidirectional"))
    )
    (net (code "134") (name "unconnected-(U2-(WR)PG0-Pad51)") (class "Default")
      (node (ref "U2") (pin "51") (pinfunction "(WR)PG0_51") (pintype "bidirectional"))
    )
    (net (code "135") (name "unconnected-(U2-(XCK0{slash}AIN0)PE2-Pad4)") (class "Default")
      (node (ref "U2") (pin "4") (pinfunction "(XCK0/AIN0)PE2_4") (pintype "bidirectional"))
    )
    (net (code "136") (name "unconnected-(U2-(XCK1)PD5-Pad48)") (class "Default")
      (node (ref "U2") (pin "48") (pinfunction "(XCK1)PD5_48") (pintype "bidirectional"))
    )
    (net (code "137") (name "unconnected-(U2-PH2(XCK2)-Pad14)") (class "Default")
      (node (ref "U2") (pin "14") (pinfunction "PH2(XCK2)_14") (pintype "bidirectional"))
    )
    (net (code "138") (name "unconnected-(U2-PH7(T4)-Pad27)") (class "Default")
      (node (ref "U2") (pin "27") (pinfunction "PH7(T4)_27") (pintype "bidirectional"))
    )
    (net (code "139") (name "unconnected-(U2-PJ0(RXD3{slash}PCINT9)-Pad63)") (class "Default")
      (node (ref "U2") (pin "63") (pinfunction "PJ0(RXD3/PCINT9)_63") (pintype "bidirectional"))
    )
    (net (code "140") (name "unconnected-(U2-PJ1(TXD3{slash}PCINT10)-Pad64)") (class "Default")
      (node (ref "U2") (pin "64") (pinfunction "PJ1(TXD3/PCINT10)_64") (pintype "bidirectional"))
    )
    (net (code "141") (name "unconnected-(U2-PJ2(XCK3{slash}PCINT11)-Pad65)") (class "Default")
      (node (ref "U2") (pin "65") (pinfunction "PJ2(XCK3/PCINT11)_65") (pintype "bidirectional"))
    )
    (net (code "142") (name "unconnected-(U2-PJ3(PCINT12)-Pad66)") (class "Default")
      (node (ref "U2") (pin "66") (pinfunction "PJ3(PCINT12)_66") (pintype "bidirectional"))
    )
    (net (code "143") (name "unconnected-(U2-PJ4(PCINT13)-Pad67)") (class "Default")
      (node (ref "U2") (pin "67") (pinfunction "PJ4(PCINT13)_67") (pintype "bidirectional"))
    )
    (net (code "144") (name "unconnected-(U2-PJ5(PCINT14)-Pad68)") (class "Default")
      (node (ref "U2") (pin "68") (pinfunction "PJ5(PCINT14)_68") (pintype "bidirectional"))
    )
    (net (code "145") (name "unconnected-(U2-PJ6(PCINT15)-Pad69)") (class "Default")
      (node (ref "U2") (pin "69") (pinfunction "PJ6(PCINT15)_69") (pintype "bidirectional"))
    )
    (net (code "146") (name "unconnected-(U2-PJ7-Pad79)") (class "Default")
      (node (ref "U2") (pin "79") (pinfunction "PJ7_79") (pintype "bidirectional"))
    )
    (net (code "147") (name "unconnected-(U2-PK0(ADC8{slash}PCINT16)-Pad89)") (class "Default")
      (node (ref "U2") (pin "89") (pinfunction "PK0(ADC8/PCINT16)_89") (pintype "bidirectional"))
    )
    (net (code "148") (name "unconnected-(U2-PK1(ADC9{slash}PCINT17)-Pad88)") (class "Default")
      (node (ref "U2") (pin "88") (pinfunction "PK1(ADC9/PCINT17)_88") (pintype "bidirectional"))
    )
    (net (code "149") (name "unconnected-(U2-PK2(ADC10{slash}PCINT18)-Pad87)") (class "Default")
      (node (ref "U2") (pin "87") (pinfunction "PK2(ADC10/PCINT18)_87") (pintype "bidirectional"))
    )
    (net (code "150") (name "unconnected-(U2-PK3(ADC11{slash}PCINT19)-Pad86)") (class "Default")
      (node (ref "U2") (pin "86") (pinfunction "PK3(ADC11/PCINT19)_86") (pintype "bidirectional"))
    )
    (net (code "151") (name "unconnected-(U2-PK4(ADC12{slash}PCINT20)-Pad85)") (class "Default")
      (node (ref "U2") (pin "85") (pinfunction "PK4(ADC12/PCINT20)_85") (pintype "bidirectional"))
    )
    (net (code "152") (name "unconnected-(U2-PK5(ADC13{slash}PCINT21)-Pad84)") (class "Default")
      (node (ref "U2") (pin "84") (pinfunction "PK5(ADC13/PCINT21)_84") (pintype "bidirectional"))
    )
    (net (code "153") (name "unconnected-(U2-PK6(ADC14{slash}PCINT22)-Pad83)") (class "Default")
      (node (ref "U2") (pin "83") (pinfunction "PK6(ADC14/PCINT22)_83") (pintype "bidirectional"))
    )
    (net (code "154") (name "unconnected-(U2-PK7(ADC15{slash}PCINT23)-Pad82)") (class "Default")
      (node (ref "U2") (pin "82") (pinfunction "PK7(ADC15/PCINT23)_82") (pintype "bidirectional"))
    )
    (net (code "155") (name "unconnected-(U2-PL0(ICP4)-Pad35)") (class "Default")
      (node (ref "U2") (pin "35") (pinfunction "PL0(ICP4)_35") (pintype "bidirectional"))
    )
    (net (code "156") (name "unconnected-(U2-PL1(ICP5)-Pad36)") (class "Default")
      (node (ref "U2") (pin "36") (pinfunction "PL1(ICP5)_36") (pintype "bidirectional"))
    )
    (net (code "157") (name "unconnected-(U2-PL2(T5)-Pad37)") (class "Default")
      (node (ref "U2") (pin "37") (pinfunction "PL2(T5)_37") (pintype "bidirectional"))
    )
    (net (code "158") (name "unconnected-(U2-PL3(OC5A)-Pad38)") (class "Default")
      (node (ref "U2") (pin "38") (pinfunction "PL3(OC5A)_38") (pintype "bidirectional"))
    )
    (net (code "159") (name "unconnected-(U2-PL4(OC5B)-Pad39)") (class "Default")
      (node (ref "U2") (pin "39") (pinfunction "PL4(OC5B)_39") (pintype "bidirectional"))
    )
    (net (code "160") (name "unconnected-(U2-PL5(OC5C)-Pad40)") (class "Default")
      (node (ref "U2") (pin "40") (pinfunction "PL5(OC5C)_40") (pintype "bidirectional"))
    )
    (net (code "161") (name "unconnected-(U2-PL6-Pad41)") (class "Default")
      (node (ref "U2") (pin "41") (pinfunction "PL6_41") (pintype "bidirectional"))
    )
    (net (code "162") (name "unconnected-(U2-PL7-Pad42)") (class "Default")
      (node (ref "U2") (pin "42") (pinfunction "PL7_42") (pintype "bidirectional"))
    )
    (net (code "163") (name "unconnected-(U6-PB0-Pad14)") (class "Default")
      (node (ref "U6") (pin "14") (pinfunction "PB0_14") (pintype "bidirectional"))
    )
    (net (code "164") (name "unconnected-(U6-PB1(SCK)-Pad15)") (class "Default")
      (node (ref "U6") (pin "15") (pinfunction "PB1(SCK)_15") (pintype "bidirectional"))
    )
    (net (code "165") (name "unconnected-(U6-PB2(MOSI)-Pad16)") (class "Default")
      (node (ref "U6") (pin "16") (pinfunction "PB2(MOSI)_16") (pintype "bidirectional"))
    )
    (net (code "166") (name "unconnected-(U6-PB3(MISO)-Pad17)") (class "Default")
      (node (ref "U6") (pin "17") (pinfunction "PB3(MISO)_17") (pintype "bidirectional"))
    )
    (net (code "167") (name "unconnected-(U6-PB4-Pad18)") (class "Default")
      (node (ref "U6") (pin "18") (pinfunction "PB4_18") (pintype "bidirectional"))
    )
    (net (code "168") (name "unconnected-(U6-PB5-Pad19)") (class "Default")
      (node (ref "U6") (pin "19") (pinfunction "PB5_19") (pintype "bidirectional"))
    )
    (net (code "169") (name "unconnected-(U6-PB6-Pad20)") (class "Default")
      (node (ref "U6") (pin "20") (pinfunction "PB6_20") (pintype "bidirectional"))
    )
    (net (code "170") (name "unconnected-(U6-PB7-Pad21)") (class "Default")
      (node (ref "U6") (pin "21") (pinfunction "PB7_21") (pintype "bidirectional"))
    )
    (net (code "171") (name "unconnected-(U6-PC2-Pad5)") (class "Default")
      (node (ref "U6") (pin "5") (pinfunction "PC2_5") (pintype "bidirectional"))
    )
    (net (code "172") (name "unconnected-(U6-PC4-Pad26)") (class "Default")
      (node (ref "U6") (pin "26") (pinfunction "PC4_26") (pintype "bidirectional"))
    )
    (net (code "173") (name "unconnected-(U6-PC5-Pad25)") (class "Default")
      (node (ref "U6") (pin "25") (pinfunction "PC5_25") (pintype "bidirectional"))
    )
    (net (code "174") (name "unconnected-(U6-PC6-Pad23)") (class "Default")
      (node (ref "U6") (pin "23") (pinfunction "PC6_23") (pintype "bidirectional"))
    )
    (net (code "175") (name "unconnected-(U6-PC7-Pad22)") (class "Default")
      (node (ref "U6") (pin "22") (pinfunction "PC7_22") (pintype "bidirectional"))
    )
    (net (code "176") (name "unconnected-(U6-PD0-Pad6)") (class "Default")
      (node (ref "U6") (pin "6") (pinfunction "PD0_6") (pintype "bidirectional"))
    )
    (net (code "177") (name "unconnected-(U6-PD1-Pad7)") (class "Default")
      (node (ref "U6") (pin "7") (pinfunction "PD1_7") (pintype "bidirectional"))
    )
    (net (code "178") (name "unconnected-(U6-PD4-Pad10)") (class "Default")
      (node (ref "U6") (pin "10") (pinfunction "PD4_10") (pintype "bidirectional"))
    )
    (net (code "179") (name "unconnected-(U6-PD5-Pad11)") (class "Default")
      (node (ref "U6") (pin "11") (pinfunction "PD5_11") (pintype "bidirectional"))
    )
    (net (code "180") (name "unconnected-(U6-PD6(RTS)-Pad12)") (class "Default")
      (node (ref "U6") (pin "12") (pinfunction "PD6(RTS)_12") (pintype "bidirectional"))
    )
    (net (code "181") (name "unconnected-(U6-PD7(CTS)-Pad13)") (class "Default")
      (node (ref "U6") (pin "13") (pinfunction "PD7(CTS)_13") (pintype "bidirectional"))
    )
    (net (code "182") (name "unconnected-(U6-UVCC-Pad31)") (class "Default")
      (node (ref "U6") (pin "31") (pinfunction "UVCC_31") (pintype "bidirectional"))
    )
  )
)
